# lief-p0r1.net
KiCad netlist of a schematic drawn in EAGLE
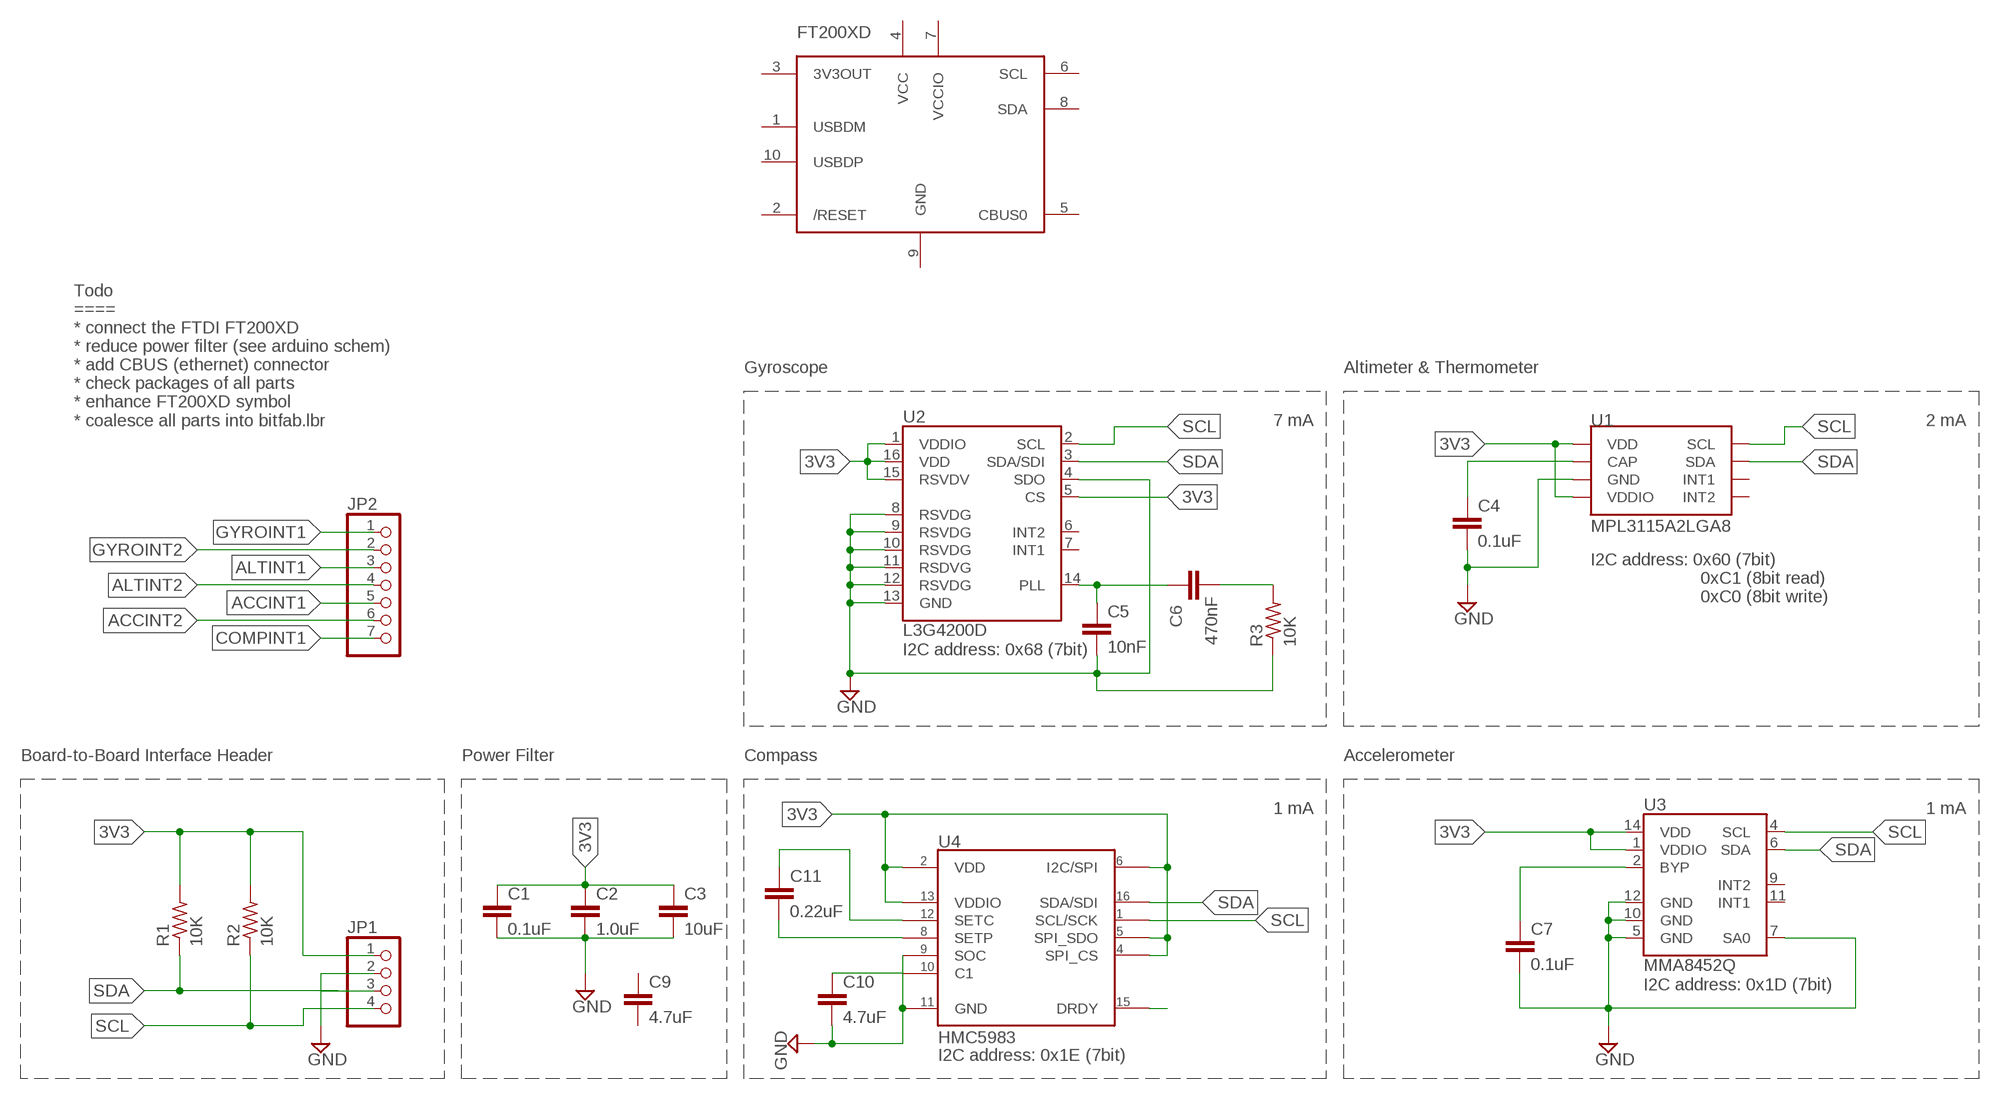
[diagram p0: schematic, sheet 1]

(export (version "E")
  (design (tool "Eeschema 10.0.6"))
  (components
    (comp (ref "C1")
      (value "0.1uF")
      (footprint "eagle-import:0603-CAP")
      (libsource (lib "eagle-import") (part "0.1UF-25V(+80/-20%)(0603)"))
    )
    (comp (ref "C2")
      (value "1.0uF")
      (footprint "eagle-import:0805-CAP")
      (libsource (lib "eagle-import") (part "1.0UF-25V-+80/-20(0805){dblquote}"))
    )
    (comp (ref "C3")
      (value "10uF")
      (footprint "eagle-import:0805-CAP")
      (libsource (lib "eagle-import") (part "1.0UF-25V-+80/-20(0805){dblquote}"))
    )
    (comp (ref "C4")
      (value "0.1uF")
      (footprint "eagle-import:0805-CAP")
      (libsource (lib "eagle-import") (part "1.0UF-25V-+80/-20(0805){dblquote}"))
    )
    (comp (ref "C5")
      (value "10nF")
      (footprint "eagle-import:0805-CAP")
      (libsource (lib "eagle-import") (part "1.0UF-25V-+80/-20(0805){dblquote}"))
    )
    (comp (ref "C6")
      (value "470nF")
      (footprint "eagle-import:0805-CAP")
      (libsource (lib "eagle-import") (part "1.0UF-25V-+80/-20(0805){dblquote}"))
    )
    (comp (ref "C7")
      (value "0.1uF")
      (footprint "eagle-import:0603-CAP")
      (libsource (lib "eagle-import") (part "0.1UF-100V-10%(0603)"))
    )
    (comp (ref "C9")
      (value "4.7uF")
      (footprint "eagle-import:0603-CAP")
      (libsource (lib "eagle-import") (part "0.1UF-100V-10%(0603)"))
    )
    (comp (ref "C10")
      (value "4.7uF")
      (footprint "eagle-import:0805-CAP")
      (libsource (lib "eagle-import") (part "1.0UF-25V-+80/-20(0805){dblquote}"))
    )
    (comp (ref "C11")
      (value "0.22uF")
      (footprint "eagle-import:0805-CAP")
      (libsource (lib "eagle-import") (part "1.0UF-25V-+80/-20(0805){dblquote}"))
    )
    (comp (ref "JP1")
      (value "PINHD-1X4")
      (footprint "eagle-import:1X04")
      (libsource (lib "eagle-import") (part "PINHD-1X4"))
    )
    (comp (ref "JP2")
      (value "PINHD-1X7")
      (footprint "eagle-import:1X07")
      (libsource (lib "eagle-import") (part "PINHD-1X7"))
    )
    (comp (ref "R1")
      (value "10K")
      (footprint "eagle-import:0204V")
      (libsource (lib "eagle-import") (part "R-US_0204/2V"))
    )
    (comp (ref "R2")
      (value "10K")
      (footprint "eagle-import:0204V")
      (libsource (lib "eagle-import") (part "R-US_0204/2V"))
    )
    (comp (ref "R3")
      (value "10K")
      (footprint "eagle-import:0204V")
      (libsource (lib "eagle-import") (part "R-US_0204/2V"))
    )
    (comp (ref "U$1")
      (value "FT200XD")
      (footprint "eagle-import:DFN-10")
      (libsource (lib "eagle-import") (part "FT200XD"))
    )
    (comp (ref "U1")
      (value "MPL3115A2LGA8")
      (footprint "eagle-import:LGA8")
      (libsource (lib "eagle-import") (part "MPL3115A2LGA8"))
    )
    (comp (ref "U2")
      (value "L3G4200D")
      (footprint "eagle-import:LGA16-4X4")
      (libsource (lib "eagle-import") (part "L3G4200D"))
    )
    (comp (ref "U3")
      (value "MMA8452Q")
      (footprint "eagle-import:QFN-16_0.5MM")
      (libsource (lib "eagle-import") (part "MMA8452Q"))
    )
    (comp (ref "U4")
      (value "HMC5983")
      (footprint "eagle-import:HMC5983-LPCC16")
      (libsource (lib "eagle-import") (part "HMC5983"))
    )
  )
  (nets
    (net (code "1") (name "3V3") (class "Default")
      (node (ref "C1") (pin "1") (pinfunction "1_1") (pintype "passive"))
      (node (ref "C2") (pin "1") (pinfunction "1_1") (pintype "passive"))
      (node (ref "C3") (pin "1") (pinfunction "1_1") (pintype "passive"))
      (node (ref "JP1") (pin "1") (pinfunction "1_1") (pintype "passive"))
      (node (ref "R1") (pin "2") (pinfunction "2_2") (pintype "passive"))
      (node (ref "R2") (pin "2") (pinfunction "2_2") (pintype "passive"))
      (node (ref "U1") (pin "1") (pinfunction "VDD_1") (pintype "power_in"))
      (node (ref "U1") (pin "4") (pinfunction "VDDIO_4") (pintype "power_in"))
      (node (ref "U2") (pin "1") (pinfunction "VDDIO_1") (pintype "bidirectional"))
      (node (ref "U2") (pin "15") (pinfunction "RSVDV_15") (pintype "bidirectional"))
      (node (ref "U2") (pin "16") (pinfunction "VDD_16") (pintype "bidirectional"))
      (node (ref "U2") (pin "5") (pinfunction "CS_5") (pintype "bidirectional"))
      (node (ref "U3") (pin "1") (pinfunction "VDDIO_1") (pintype "bidirectional"))
      (node (ref "U3") (pin "14") (pinfunction "VDD_14") (pintype "bidirectional"))
      (node (ref "U4") (pin "I2C/SPI") (pinfunction "I2C/SPI_I2C/SPI") (pintype "bidirectional"))
      (node (ref "U4") (pin "SPI_CS/S1") (pinfunction "SPI_CS_SPI_CS/S1") (pintype "bidirectional"))
      (node (ref "U4") (pin "SPI_SDO") (pinfunction "SPI_SDO_SPI_SDO") (pintype "bidirectional"))
      (node (ref "U4") (pin "VDD") (pinfunction "VDD_VDD") (pintype "power_in"))
      (node (ref "U4") (pin "VDDIO") (pinfunction "VDDIO_VDDIO") (pintype "power_in"))
    )
    (net (code "2") (name "ACCINT1") (class "Default")
      (node (ref "JP2") (pin "5") (pinfunction "5_5") (pintype "passive"))
    )
    (net (code "3") (name "ACCINT2") (class "Default")
      (node (ref "JP2") (pin "6") (pinfunction "6_6") (pintype "passive"))
    )
    (net (code "4") (name "ALTINT1") (class "Default")
      (node (ref "JP2") (pin "3") (pinfunction "3_3") (pintype "passive"))
    )
    (net (code "5") (name "ALTINT2") (class "Default")
      (node (ref "JP2") (pin "4") (pinfunction "4_4") (pintype "passive"))
    )
    (net (code "6") (name "COMPINT1") (class "Default")
      (node (ref "JP2") (pin "7") (pinfunction "7_7") (pintype "passive"))
    )
    (net (code "7") (name "GND") (class "Default")
      (node (ref "C1") (pin "2") (pinfunction "2_2") (pintype "passive"))
      (node (ref "C10") (pin "2") (pinfunction "2_2") (pintype "passive"))
      (node (ref "C2") (pin "2") (pinfunction "2_2") (pintype "passive"))
      (node (ref "C3") (pin "2") (pinfunction "2_2") (pintype "passive"))
      (node (ref "C4") (pin "2") (pinfunction "2_2") (pintype "passive"))
      (node (ref "C5") (pin "2") (pinfunction "2_2") (pintype "passive"))
      (node (ref "C7") (pin "2") (pinfunction "2_2") (pintype "passive"))
      (node (ref "JP1") (pin "2") (pinfunction "2_2") (pintype "passive"))
      (node (ref "JP1") (pin "3") (pinfunction "3_3") (pintype "passive"))
      (node (ref "R3") (pin "1") (pinfunction "1_1") (pintype "passive"))
      (node (ref "U1") (pin "3") (pinfunction "GND_3") (pintype "power_in"))
      (node (ref "U2") (pin "10") (pinfunction "RSVDG_10") (pintype "bidirectional"))
      (node (ref "U2") (pin "11") (pinfunction "RSDVG_11") (pintype "bidirectional"))
      (node (ref "U2") (pin "12") (pinfunction "RSVDG_12") (pintype "bidirectional"))
      (node (ref "U2") (pin "13") (pinfunction "GND_13") (pintype "bidirectional"))
      (node (ref "U2") (pin "4") (pinfunction "SDO_4") (pintype "bidirectional"))
      (node (ref "U2") (pin "8") (pinfunction "RSVDG_8") (pintype "bidirectional"))
      (node (ref "U2") (pin "9") (pinfunction "RSVDG_9") (pintype "bidirectional"))
      (node (ref "U3") (pin "10") (pinfunction "GND_10") (pintype "bidirectional"))
      (node (ref "U3") (pin "12") (pinfunction "GND_12") (pintype "bidirectional"))
      (node (ref "U3") (pin "5") (pinfunction "GND_5") (pintype "bidirectional"))
      (node (ref "U3") (pin "7") (pinfunction "SA0_7") (pintype "bidirectional"))
      (node (ref "U4") (pin "GND") (pinfunction "GND_GND") (pintype "power_in"))
      (node (ref "U4") (pin "SOC") (pinfunction "SOC_SOC") (pintype "bidirectional"))
    )
    (net (code "8") (name "GYROINT1") (class "Default")
      (node (ref "JP2") (pin "1") (pinfunction "1_1") (pintype "passive"))
    )
    (net (code "9") (name "GYROINT2") (class "Default")
      (node (ref "JP2") (pin "2") (pinfunction "2_2") (pintype "passive"))
    )
    (net (code "10") (name "Net-(C6-Pad2)") (class "Default")
      (node (ref "C6") (pin "2") (pinfunction "2_2") (pintype "passive"))
      (node (ref "R3") (pin "2") (pinfunction "2_2") (pintype "passive"))
    )
    (net (code "11") (name "Net-(C10-Pad1)") (class "Default")
      (node (ref "C10") (pin "1") (pinfunction "1_1") (pintype "passive"))
      (node (ref "U4") (pin "C1") (pinfunction "C1_C1") (pintype "bidirectional"))
    )
    (net (code "12") (name "Net-(C11-Pad1)") (class "Default")
      (node (ref "C11") (pin "1") (pinfunction "1_1") (pintype "passive"))
      (node (ref "U4") (pin "SETC") (pinfunction "SETC_SETC") (pintype "bidirectional"))
    )
    (net (code "13") (name "Net-(C11-Pad2)") (class "Default")
      (node (ref "C11") (pin "2") (pinfunction "2_2") (pintype "passive"))
      (node (ref "U4") (pin "SETP") (pinfunction "SETP_SETP") (pintype "bidirectional"))
    )
    (net (code "14") (name "Net-(U1-CAP)") (class "Default")
      (node (ref "C4") (pin "1") (pinfunction "1_1") (pintype "passive"))
      (node (ref "U1") (pin "2") (pinfunction "CAP_2") (pintype "power_in"))
    )
    (net (code "15") (name "Net-(U2-PLL)") (class "Default")
      (node (ref "C5") (pin "1") (pinfunction "1_1") (pintype "passive"))
      (node (ref "C6") (pin "1") (pinfunction "1_1") (pintype "passive"))
      (node (ref "U2") (pin "14") (pinfunction "PLL_14") (pintype "bidirectional"))
    )
    (net (code "16") (name "Net-(U3-BYP)") (class "Default")
      (node (ref "C7") (pin "1") (pinfunction "1_1") (pintype "passive"))
      (node (ref "U3") (pin "2") (pinfunction "BYP_2") (pintype "bidirectional"))
    )
    (net (code "17") (name "SCL") (class "Default")
      (node (ref "JP1") (pin "4") (pinfunction "4_4") (pintype "passive"))
      (node (ref "R2") (pin "1") (pinfunction "1_1") (pintype "passive"))
      (node (ref "U1") (pin "8") (pinfunction "SCL_8") (pintype "bidirectional"))
      (node (ref "U2") (pin "2") (pinfunction "SCL_2") (pintype "bidirectional"))
      (node (ref "U3") (pin "4") (pinfunction "SCL_4") (pintype "bidirectional"))
      (node (ref "U4") (pin "SCL/SPI_SCK") (pinfunction "SCL/SCK_SCL/SPI_SCK") (pintype "bidirectional"))
    )
    (net (code "18") (name "SDA") (class "Default")
      (node (ref "R1") (pin "1") (pinfunction "1_1") (pintype "passive"))
      (node (ref "U1") (pin "7") (pinfunction "SDA_7") (pintype "bidirectional"))
      (node (ref "U2") (pin "3") (pinfunction "SDA/SDI_3") (pintype "bidirectional"))
      (node (ref "U3") (pin "6") (pinfunction "SDA_6") (pintype "bidirectional"))
      (node (ref "U4") (pin "SDA/SPI_SDI") (pinfunction "SDA/SDI_SDA/SPI_SDI") (pintype "bidirectional"))
    )
    (net (code "19") (name "unconnected-(C9-Pad1)") (class "Default")
      (node (ref "C9") (pin "1") (pinfunction "1_1") (pintype "passive"))
    )
    (net (code "20") (name "unconnected-(C9-Pad2)") (class "Default")
      (node (ref "C9") (pin "2") (pinfunction "2_2") (pintype "passive"))
    )
    (net (code "21") (name "unconnected-(U$1-3V3OUT-Pad3)") (class "Default")
      (node (ref "U$1") (pin "3") (pinfunction "3V3OUT_3") (pintype "bidirectional"))
    )
    (net (code "22") (name "unconnected-(U$1-CBUS0-Pad5)") (class "Default")
      (node (ref "U$1") (pin "5") (pinfunction "CBUS0_5") (pintype "bidirectional"))
    )
    (net (code "23") (name "unconnected-(U$1-GND-Pad9)") (class "Default")
      (node (ref "U$1") (pin "9") (pinfunction "GND_9") (pintype "bidirectional"))
    )
    (net (code "24") (name "unconnected-(U$1-SCL-Pad6)") (class "Default")
      (node (ref "U$1") (pin "6") (pinfunction "SCL_6") (pintype "bidirectional"))
    )
    (net (code "25") (name "unconnected-(U$1-SDA-Pad8)") (class "Default")
      (node (ref "U$1") (pin "8") (pinfunction "SDA_8") (pintype "bidirectional"))
    )
    (net (code "26") (name "unconnected-(U$1-USBDM-Pad1)") (class "Default")
      (node (ref "U$1") (pin "1") (pinfunction "USBDM_1") (pintype "bidirectional"))
    )
    (net (code "27") (name "unconnected-(U$1-USBDP-Pad10)") (class "Default")
      (node (ref "U$1") (pin "10") (pinfunction "USBDP_10") (pintype "bidirectional"))
    )
    (net (code "28") (name "unconnected-(U$1-VCC-Pad4)") (class "Default")
      (node (ref "U$1") (pin "4") (pinfunction "VCC_4") (pintype "bidirectional"))
    )
    (net (code "29") (name "unconnected-(U$1-VCCIO-Pad7)") (class "Default")
      (node (ref "U$1") (pin "7") (pinfunction "VCCIO_7") (pintype "bidirectional"))
    )
    (net (code "30") (name "unconnected-(U$1-{slash}RESET-Pad2)") (class "Default")
      (node (ref "U$1") (pin "2") (pinfunction "/RESET_2") (pintype "bidirectional"))
    )
    (net (code "31") (name "unconnected-(U1-INT1-Pad6)") (class "Default")
      (node (ref "U1") (pin "6") (pinfunction "INT1_6") (pintype "output"))
    )
    (net (code "32") (name "unconnected-(U1-INT2-Pad5)") (class "Default")
      (node (ref "U1") (pin "5") (pinfunction "INT2_5") (pintype "output"))
    )
    (net (code "33") (name "unconnected-(U2-INT1-Pad7)") (class "Default")
      (node (ref "U2") (pin "7") (pinfunction "INT1_7") (pintype "bidirectional"))
    )
    (net (code "34") (name "unconnected-(U2-INT2-Pad6)") (class "Default")
      (node (ref "U2") (pin "6") (pinfunction "INT2_6") (pintype "bidirectional"))
    )
    (net (code "35") (name "unconnected-(U3-INT1-Pad11)") (class "Default")
      (node (ref "U3") (pin "11") (pinfunction "INT1_11") (pintype "bidirectional"))
    )
    (net (code "36") (name "unconnected-(U3-INT2-Pad9)") (class "Default")
      (node (ref "U3") (pin "9") (pinfunction "INT2_9") (pintype "bidirectional"))
    )
    (net (code "37") (name "unconnected-(U4-PadDRDY)") (class "Default")
      (node (ref "U4") (pin "DRDY") (pinfunction "DRDY_DRDY") (pintype "bidirectional"))
    )
  )
)
